# kot.net
KiCad netlist of a schematic drawn in EAGLE
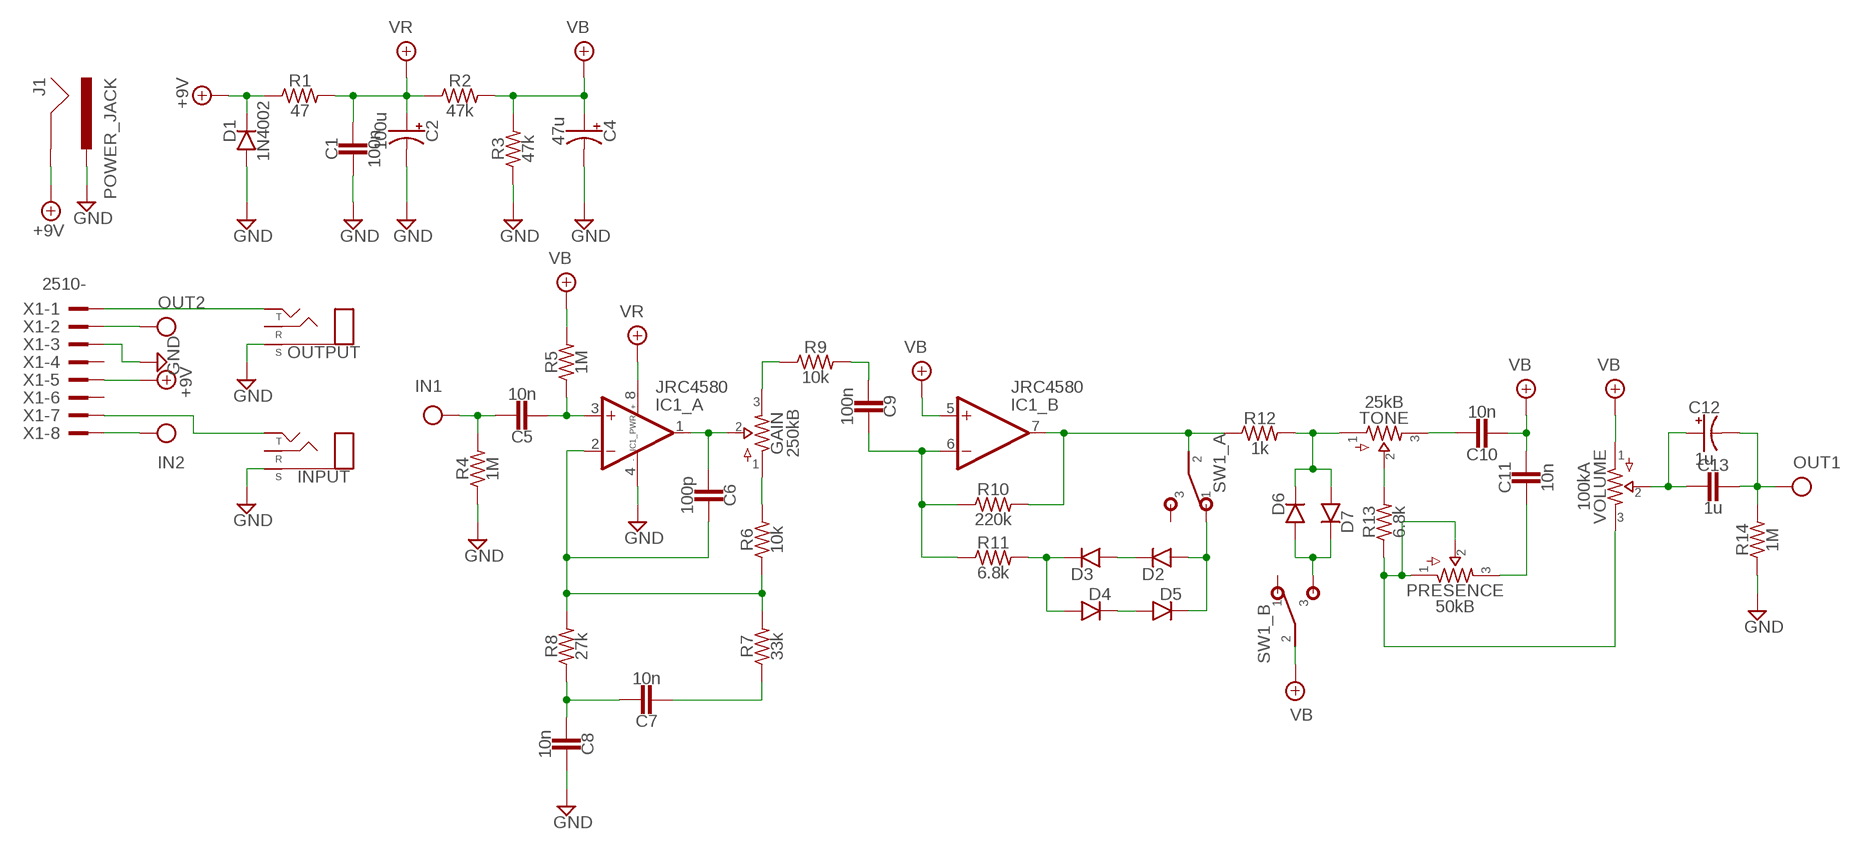
[diagram p0: schematic, sheet 1]

(export (version "E")
  (design (tool "Eeschema 10.0.6"))
  (components
    (comp (ref "C1")
      (value "100n")
      (footprint "eagle-import:050X030_025_2")
      (libsource (lib "eagle-import") (part "CER/FILM2"))
    )
    (comp (ref "C2")
      (value "100u")
      (footprint "eagle-import:050_020")
      (libsource (lib "eagle-import") (part "0500"))
    )
    (comp (ref "C4")
      (value "47u")
      (footprint "eagle-import:050_020")
      (libsource (lib "eagle-import") (part "0500"))
    )
    (comp (ref "C5")
      (value "10n")
      (footprint "eagle-import:BOX_SMALL")
      (libsource (lib "eagle-import") (part "CER/FILMBOX.1"))
    )
    (comp (ref "C6")
      (value "100p")
      (footprint "eagle-import:050X030_025_2")
      (libsource (lib "eagle-import") (part "CER/FILM2"))
    )
    (comp (ref "C7")
      (value "10n")
      (footprint "eagle-import:BOX_SMALL")
      (libsource (lib "eagle-import") (part "CER/FILMBOX.1"))
    )
    (comp (ref "C8")
      (value "10n")
      (footprint "eagle-import:BOX_SMALL")
      (libsource (lib "eagle-import") (part "CER/FILMBOX.1"))
    )
    (comp (ref "C9")
      (value "100n")
      (footprint "eagle-import:BOX_SMALL")
      (libsource (lib "eagle-import") (part "CER/FILMBOX.1"))
    )
    (comp (ref "C10")
      (value "10n")
      (footprint "eagle-import:BOX_SMALL")
      (libsource (lib "eagle-import") (part "CER/FILMBOX.1"))
    )
    (comp (ref "C11")
      (value "10n")
      (footprint "eagle-import:BOX_SMALL")
      (libsource (lib "eagle-import") (part "CER/FILMBOX.1"))
    )
    (comp (ref "C12")
      (value "1u")
      (footprint "eagle-import:040_020")
      (libsource (lib "eagle-import") (part "0400"))
    )
    (comp (ref "C13")
      (value "1u")
      (footprint "eagle-import:BOX_BIG")
      (libsource (lib "eagle-import") (part "CER/FILMBOX.3"))
    )
    (comp (ref "D1")
      (value "1N4002")
      (footprint "eagle-import:DO41-2")
      (libsource (lib "eagle-import") (part "DO41.2"))
    )
    (comp (ref "D2")
      (value "DO35.2")
      (footprint "eagle-import:DO35-2")
      (libsource (lib "eagle-import") (part "DO35.2"))
    )
    (comp (ref "D3")
      (value "DO35.2")
      (footprint "eagle-import:DO35-2")
      (libsource (lib "eagle-import") (part "DO35.2"))
    )
    (comp (ref "D4")
      (value "DO35.2")
      (footprint "eagle-import:DO35-2")
      (libsource (lib "eagle-import") (part "DO35.2"))
    )
    (comp (ref "D5")
      (value "DO35.2")
      (footprint "eagle-import:DO35-2")
      (libsource (lib "eagle-import") (part "DO35.2"))
    )
    (comp (ref "D6")
      (value "DO35.2")
      (footprint "eagle-import:DO35-2")
      (libsource (lib "eagle-import") (part "DO35.2"))
    )
    (comp (ref "D7")
      (value "DO35.2")
      (footprint "eagle-import:DO35-2")
      (libsource (lib "eagle-import") (part "DO35.2"))
    )
    (comp (ref "GAIN")
      (value "250kB")
      (footprint "eagle-import:16MM")
      (libsource (lib "eagle-import") (part "POTS16MM"))
    )
    (comp (ref "IC1")
      (value "JRC4580")
      (footprint "eagle-import:DIL08")
      (libsource (lib "eagle-import") (part "DUALTH"))
    )
    (comp (ref "INPUT")
      (value "STEREONMJ")
      (footprint "eagle-import:NMJ6HCD2")
      (libsource (lib "eagle-import") (part "STEREONMJ"))
    )
    (comp (ref "J1")
      (value "POWER_JACK")
      (footprint "eagle-import:POWER_JACK_PTH")
      (libsource (lib "eagle-import") (part "POWER_JACK"))
    )
    (comp (ref "OUTPUT")
      (value "STEREONMJ")
      (footprint "eagle-import:NMJ6HCD2")
      (libsource (lib "eagle-import") (part "STEREONMJ"))
    )
    (comp (ref "PRESENCE")
      (value "50kB")
      (footprint "eagle-import:16MM")
      (libsource (lib "eagle-import") (part "POTS16MM"))
    )
    (comp (ref "R1")
      (value "47")
      (footprint "eagle-import:R0207_3")
      (libsource (lib "eagle-import") (part "R_.3B"))
    )
    (comp (ref "R2")
      (value "47k")
      (footprint "eagle-import:R0207_3")
      (libsource (lib "eagle-import") (part "R_.3B"))
    )
    (comp (ref "R3")
      (value "47k")
      (footprint "eagle-import:R0207_3")
      (libsource (lib "eagle-import") (part "R_.3B"))
    )
    (comp (ref "R4")
      (value "1M")
      (footprint "eagle-import:R0207_3")
      (libsource (lib "eagle-import") (part "R_.3B"))
    )
    (comp (ref "R5")
      (value "1M")
      (footprint "eagle-import:R0207_3")
      (libsource (lib "eagle-import") (part "R_.3B"))
    )
    (comp (ref "R6")
      (value "10k")
      (footprint "eagle-import:R0207_3")
      (libsource (lib "eagle-import") (part "R_.3B"))
    )
    (comp (ref "R7")
      (value "33k")
      (footprint "eagle-import:R0207_3")
      (libsource (lib "eagle-import") (part "R_.3B"))
    )
    (comp (ref "R8")
      (value "27k")
      (footprint "eagle-import:R0207_3")
      (libsource (lib "eagle-import") (part "R_.3B"))
    )
    (comp (ref "R9")
      (value "10k")
      (footprint "eagle-import:R0207_3")
      (libsource (lib "eagle-import") (part "R_.3B"))
    )
    (comp (ref "R10")
      (value "220k")
      (footprint "eagle-import:R0207_3")
      (libsource (lib "eagle-import") (part "R_.3B"))
    )
    (comp (ref "R11")
      (value "6.8k")
      (footprint "eagle-import:R0207_3")
      (libsource (lib "eagle-import") (part "R_.3B"))
    )
    (comp (ref "R12")
      (value "1k")
      (footprint "eagle-import:R0207_3")
      (libsource (lib "eagle-import") (part "R_.3B"))
    )
    (comp (ref "R13")
      (value "6.8k")
      (footprint "eagle-import:R0207_3")
      (libsource (lib "eagle-import") (part "R_.3B"))
    )
    (comp (ref "R14")
      (value "1M")
      (footprint "eagle-import:R0207_3")
      (libsource (lib "eagle-import") (part "R_.3B"))
    )
    (comp (ref "SW1")
      (value "DPDT")
      (footprint "eagle-import:DPDT")
      (libsource (lib "eagle-import") (part "DPDT"))
    )
    (comp (ref "TONE")
      (value "25kB")
      (footprint "eagle-import:16MM")
      (libsource (lib "eagle-import") (part "POTS16MM"))
    )
    (comp (ref "VOLUME")
      (value "100kA")
      (footprint "eagle-import:16MM")
      (libsource (lib "eagle-import") (part "POTS16MM"))
    )
    (comp (ref "X1")
      (value "2510-")
      (footprint "eagle-import:PAK100_2500-10")
      (fields (field (name "MF") "3M") (field (name "MPN") "2510-6002UB"))
      (libsource (lib "eagle-import") (part "2510-"))
    )
  )
  (nets
    (net (code "1") (name "+9V") (class "Default")
      (node (ref "D1") (pin "C") (pinfunction "C_C") (pintype "passive"))
      (node (ref "J1") (pin "GND") (pinfunction "GND_GND") (pintype "bidirectional"))
      (node (ref "R1") (pin "1") (pinfunction "1_1") (pintype "passive"))
      (node (ref "X1") (pin "5") (pinfunction "KL_5") (pintype "passive"))
    )
    (net (code "2") (name "GND") (class "Default")
      (node (ref "C1") (pin "2") (pinfunction "2_2") (pintype "passive"))
      (node (ref "C2") (pin "-") (pinfunction "-_-") (pintype "passive"))
      (node (ref "C4") (pin "-") (pinfunction "-_-") (pintype "passive"))
      (node (ref "C8") (pin "1") (pinfunction "1_1") (pintype "passive"))
      (node (ref "D1") (pin "A") (pinfunction "A_A") (pintype "passive"))
      (node (ref "IC1") (pin "4") (pinfunction "V-_4") (pintype "power_in"))
      (node (ref "INPUT") (pin "S") (pinfunction "S_S") (pintype "passive"))
      (node (ref "J1") (pin "PWR") (pinfunction "PWR_PWR") (pintype "bidirectional"))
      (node (ref "OUTPUT") (pin "S") (pinfunction "S_S") (pintype "passive"))
      (node (ref "R14") (pin "1") (pinfunction "1_1") (pintype "passive"))
      (node (ref "R3") (pin "1") (pinfunction "1_1") (pintype "passive"))
      (node (ref "R4") (pin "1") (pinfunction "1_1") (pintype "passive"))
      (node (ref "X1") (pin "3") (pinfunction "KL_3") (pintype "passive"))
    )
    (net (code "3") (name "IN") (class "Default")
      (node (ref "C5") (pin "1") (pinfunction "1_1") (pintype "passive"))
      (node (ref "R4") (pin "2") (pinfunction "2_2") (pintype "passive"))
      (node (ref "X1") (pin "8") (pinfunction "KL_8") (pintype "passive"))
    )
    (net (code "4") (name "Net-(C7-Pad1)") (class "Default")
      (node (ref "C7") (pin "1") (pinfunction "1_1") (pintype "passive"))
      (node (ref "C8") (pin "2") (pinfunction "2_2") (pintype "passive"))
      (node (ref "R8") (pin "1") (pinfunction "1_1") (pintype "passive"))
    )
    (net (code "5") (name "Net-(C7-Pad2)") (class "Default")
      (node (ref "C7") (pin "2") (pinfunction "2_2") (pintype "passive"))
      (node (ref "R7") (pin "1") (pinfunction "1_1") (pintype "passive"))
    )
    (net (code "6") (name "Net-(C9-Pad2)") (class "Default")
      (node (ref "C9") (pin "2") (pinfunction "2_2") (pintype "passive"))
      (node (ref "R9") (pin "2") (pinfunction "2_2") (pintype "passive"))
    )
    (net (code "7") (name "Net-(C10-Pad1)") (class "Default")
      (node (ref "C10") (pin "1") (pinfunction "1_1") (pintype "passive"))
      (node (ref "TONE") (pin "3") (pinfunction "3_3") (pintype "passive"))
    )
    (net (code "8") (name "Net-(C11-Pad2)") (class "Default")
      (node (ref "C11") (pin "2") (pinfunction "2_2") (pintype "passive"))
      (node (ref "PRESENCE") (pin "3") (pinfunction "3_3") (pintype "passive"))
    )
    (net (code "9") (name "Net-(C12-Pad+)") (class "Default")
      (node (ref "C12") (pin "+") (pinfunction "+_+") (pintype "passive"))
      (node (ref "C13") (pin "2") (pinfunction "2_2") (pintype "passive"))
      (node (ref "VOLUME") (pin "2") (pinfunction "2_2") (pintype "passive"))
    )
    (net (code "10") (name "Net-(D2-PadC)") (class "Default")
      (node (ref "D2") (pin "C") (pinfunction "C_C") (pintype "passive"))
      (node (ref "D3") (pin "A") (pinfunction "A_A") (pintype "passive"))
    )
    (net (code "11") (name "Net-(D3-PadC)") (class "Default")
      (node (ref "D3") (pin "C") (pinfunction "C_C") (pintype "passive"))
      (node (ref "D4") (pin "A") (pinfunction "A_A") (pintype "passive"))
      (node (ref "R11") (pin "2") (pinfunction "2_2") (pintype "passive"))
    )
    (net (code "12") (name "Net-(D4-PadC)") (class "Default")
      (node (ref "D4") (pin "C") (pinfunction "C_C") (pintype "passive"))
      (node (ref "D5") (pin "A") (pinfunction "A_A") (pintype "passive"))
    )
    (net (code "13") (name "Net-(D6-PadC)") (class "Default")
      (node (ref "D6") (pin "C") (pinfunction "C_C") (pintype "passive"))
      (node (ref "D7") (pin "A") (pinfunction "A_A") (pintype "passive"))
      (node (ref "R12") (pin "2") (pinfunction "2_2") (pintype "passive"))
      (node (ref "TONE") (pin "1") (pinfunction "1_1") (pintype "passive"))
    )
    (net (code "14") (name "Net-(GAIN-Pad1)") (class "Default")
      (node (ref "GAIN") (pin "1") (pinfunction "1_1") (pintype "passive"))
      (node (ref "R6") (pin "2") (pinfunction "2_2") (pintype "passive"))
    )
    (net (code "15") (name "Net-(GAIN-Pad3)") (class "Default")
      (node (ref "GAIN") (pin "3") (pinfunction "3_3") (pintype "passive"))
      (node (ref "R9") (pin "1") (pinfunction "1_1") (pintype "passive"))
    )
    (net (code "16") (name "Net-(IC1A-+IN)") (class "Default")
      (node (ref "C5") (pin "2") (pinfunction "2_2") (pintype "passive"))
      (node (ref "IC1") (pin "3") (pinfunction "+IN_3") (pintype "input"))
      (node (ref "R5") (pin "1") (pinfunction "1_1") (pintype "passive"))
    )
    (net (code "17") (name "Net-(IC1A--IN)") (class "Default")
      (node (ref "C6") (pin "1") (pinfunction "1_1") (pintype "passive"))
      (node (ref "IC1") (pin "2") (pinfunction "-IN_2") (pintype "input"))
      (node (ref "R6") (pin "1") (pinfunction "1_1") (pintype "passive"))
      (node (ref "R7") (pin "2") (pinfunction "2_2") (pintype "passive"))
      (node (ref "R8") (pin "2") (pinfunction "2_2") (pintype "passive"))
    )
    (net (code "18") (name "Net-(IC1A-OUT)") (class "Default")
      (node (ref "C6") (pin "2") (pinfunction "2_2") (pintype "passive"))
      (node (ref "GAIN") (pin "2") (pinfunction "2_2") (pintype "passive"))
      (node (ref "IC1") (pin "1") (pinfunction "OUT_1") (pintype "output"))
    )
    (net (code "19") (name "Net-(IC1B--IN)") (class "Default")
      (node (ref "C9") (pin "1") (pinfunction "1_1") (pintype "passive"))
      (node (ref "IC1") (pin "6") (pinfunction "-IN_6") (pintype "input"))
      (node (ref "R10") (pin "1") (pinfunction "1_1") (pintype "passive"))
      (node (ref "R11") (pin "1") (pinfunction "1_1") (pintype "passive"))
    )
    (net (code "20") (name "Net-(IC1B-OUT)") (class "Default")
      (node (ref "IC1") (pin "7") (pinfunction "OUT_7") (pintype "output"))
      (node (ref "R10") (pin "2") (pinfunction "2_2") (pintype "passive"))
      (node (ref "R12") (pin "1") (pinfunction "1_1") (pintype "passive"))
      (node (ref "SW1") (pin "A2") (pinfunction "2_A2") (pintype "passive"))
    )
    (net (code "21") (name "Net-(PRESENCE-Pad1)") (class "Default")
      (node (ref "PRESENCE") (pin "1") (pinfunction "1_1") (pintype "passive"))
      (node (ref "PRESENCE") (pin "2") (pinfunction "2_2") (pintype "passive"))
      (node (ref "R13") (pin "1") (pinfunction "1_1") (pintype "passive"))
      (node (ref "VOLUME") (pin "3") (pinfunction "3_3") (pintype "passive"))
    )
    (net (code "22") (name "Net-(R13-Pad2)") (class "Default")
      (node (ref "R13") (pin "2") (pinfunction "2_2") (pintype "passive"))
      (node (ref "TONE") (pin "2") (pinfunction "2_2") (pintype "passive"))
    )
    (net (code "23") (name "Net-(SW1A-1)") (class "Default")
      (node (ref "D2") (pin "A") (pinfunction "A_A") (pintype "passive"))
      (node (ref "D5") (pin "C") (pinfunction "C_C") (pintype "passive"))
      (node (ref "SW1") (pin "A1") (pinfunction "1_A1") (pintype "passive"))
    )
    (net (code "24") (name "Net-(SW1B-3)") (class "Default")
      (node (ref "D6") (pin "A") (pinfunction "A_A") (pintype "passive"))
      (node (ref "D7") (pin "C") (pinfunction "C_C") (pintype "passive"))
      (node (ref "SW1") (pin "B3") (pinfunction "3_B3") (pintype "passive"))
    )
    (net (code "25") (name "Net-(X1A-KL)") (class "Default")
      (node (ref "OUTPUT") (pin "T") (pinfunction "T_T") (pintype "passive"))
      (node (ref "X1") (pin "1") (pinfunction "KL_1") (pintype "passive"))
    )
    (net (code "26") (name "Net-(X1G-KL)") (class "Default")
      (node (ref "INPUT") (pin "T") (pinfunction "T_T") (pintype "passive"))
      (node (ref "X1") (pin "7") (pinfunction "KL_7") (pintype "passive"))
    )
    (net (code "27") (name "OUT") (class "Default")
      (node (ref "C12") (pin "-") (pinfunction "-_-") (pintype "passive"))
      (node (ref "C13") (pin "1") (pinfunction "1_1") (pintype "passive"))
      (node (ref "R14") (pin "2") (pinfunction "2_2") (pintype "passive"))
      (node (ref "X1") (pin "2") (pinfunction "KL_2") (pintype "passive"))
    )
    (net (code "28") (name "VB") (class "Default")
      (node (ref "C10") (pin "2") (pinfunction "2_2") (pintype "passive"))
      (node (ref "C11") (pin "1") (pinfunction "1_1") (pintype "passive"))
      (node (ref "C4") (pin "+") (pinfunction "+_+") (pintype "passive"))
      (node (ref "IC1") (pin "5") (pinfunction "+IN_5") (pintype "input"))
      (node (ref "R2") (pin "2") (pinfunction "2_2") (pintype "passive"))
      (node (ref "R3") (pin "2") (pinfunction "2_2") (pintype "passive"))
      (node (ref "R5") (pin "2") (pinfunction "2_2") (pintype "passive"))
      (node (ref "SW1") (pin "B2") (pinfunction "2_B2") (pintype "passive"))
      (node (ref "VOLUME") (pin "1") (pinfunction "1_1") (pintype "passive"))
    )
    (net (code "29") (name "VR") (class "Default")
      (node (ref "C1") (pin "1") (pinfunction "1_1") (pintype "passive"))
      (node (ref "C2") (pin "+") (pinfunction "+_+") (pintype "passive"))
      (node (ref "IC1") (pin "8") (pinfunction "V+_8") (pintype "power_in"))
      (node (ref "R1") (pin "2") (pinfunction "2_2") (pintype "passive"))
      (node (ref "R2") (pin "1") (pinfunction "1_1") (pintype "passive"))
    )
    (net (code "30") (name "unconnected-(INPUT-PadR)") (class "Default")
      (node (ref "INPUT") (pin "R") (pinfunction "R_R") (pintype "passive"))
    )
    (net (code "31") (name "unconnected-(OUTPUT-PadR)") (class "Default")
      (node (ref "OUTPUT") (pin "R") (pinfunction "R_R") (pintype "passive"))
    )
    (net (code "32") (name "unconnected-(SW1A-3-PadA3)") (class "Default")
      (node (ref "SW1") (pin "A3") (pinfunction "3_A3") (pintype "passive"))
    )
    (net (code "33") (name "unconnected-(SW1B-1-PadB1)") (class "Default")
      (node (ref "SW1") (pin "B1") (pinfunction "1_B1") (pintype "passive"))
    )
    (net (code "34") (name "unconnected-(X1D-KL-Pad4)") (class "Default")
      (node (ref "X1") (pin "4") (pinfunction "KL_4") (pintype "passive"))
    )
    (net (code "35") (name "unconnected-(X1F-KL-Pad6)") (class "Default")
      (node (ref "X1") (pin "6") (pinfunction "KL_6") (pintype "passive"))
    )
  )
)
